# Power.net
KiCad netlist of a schematic drawn in Altium Designer
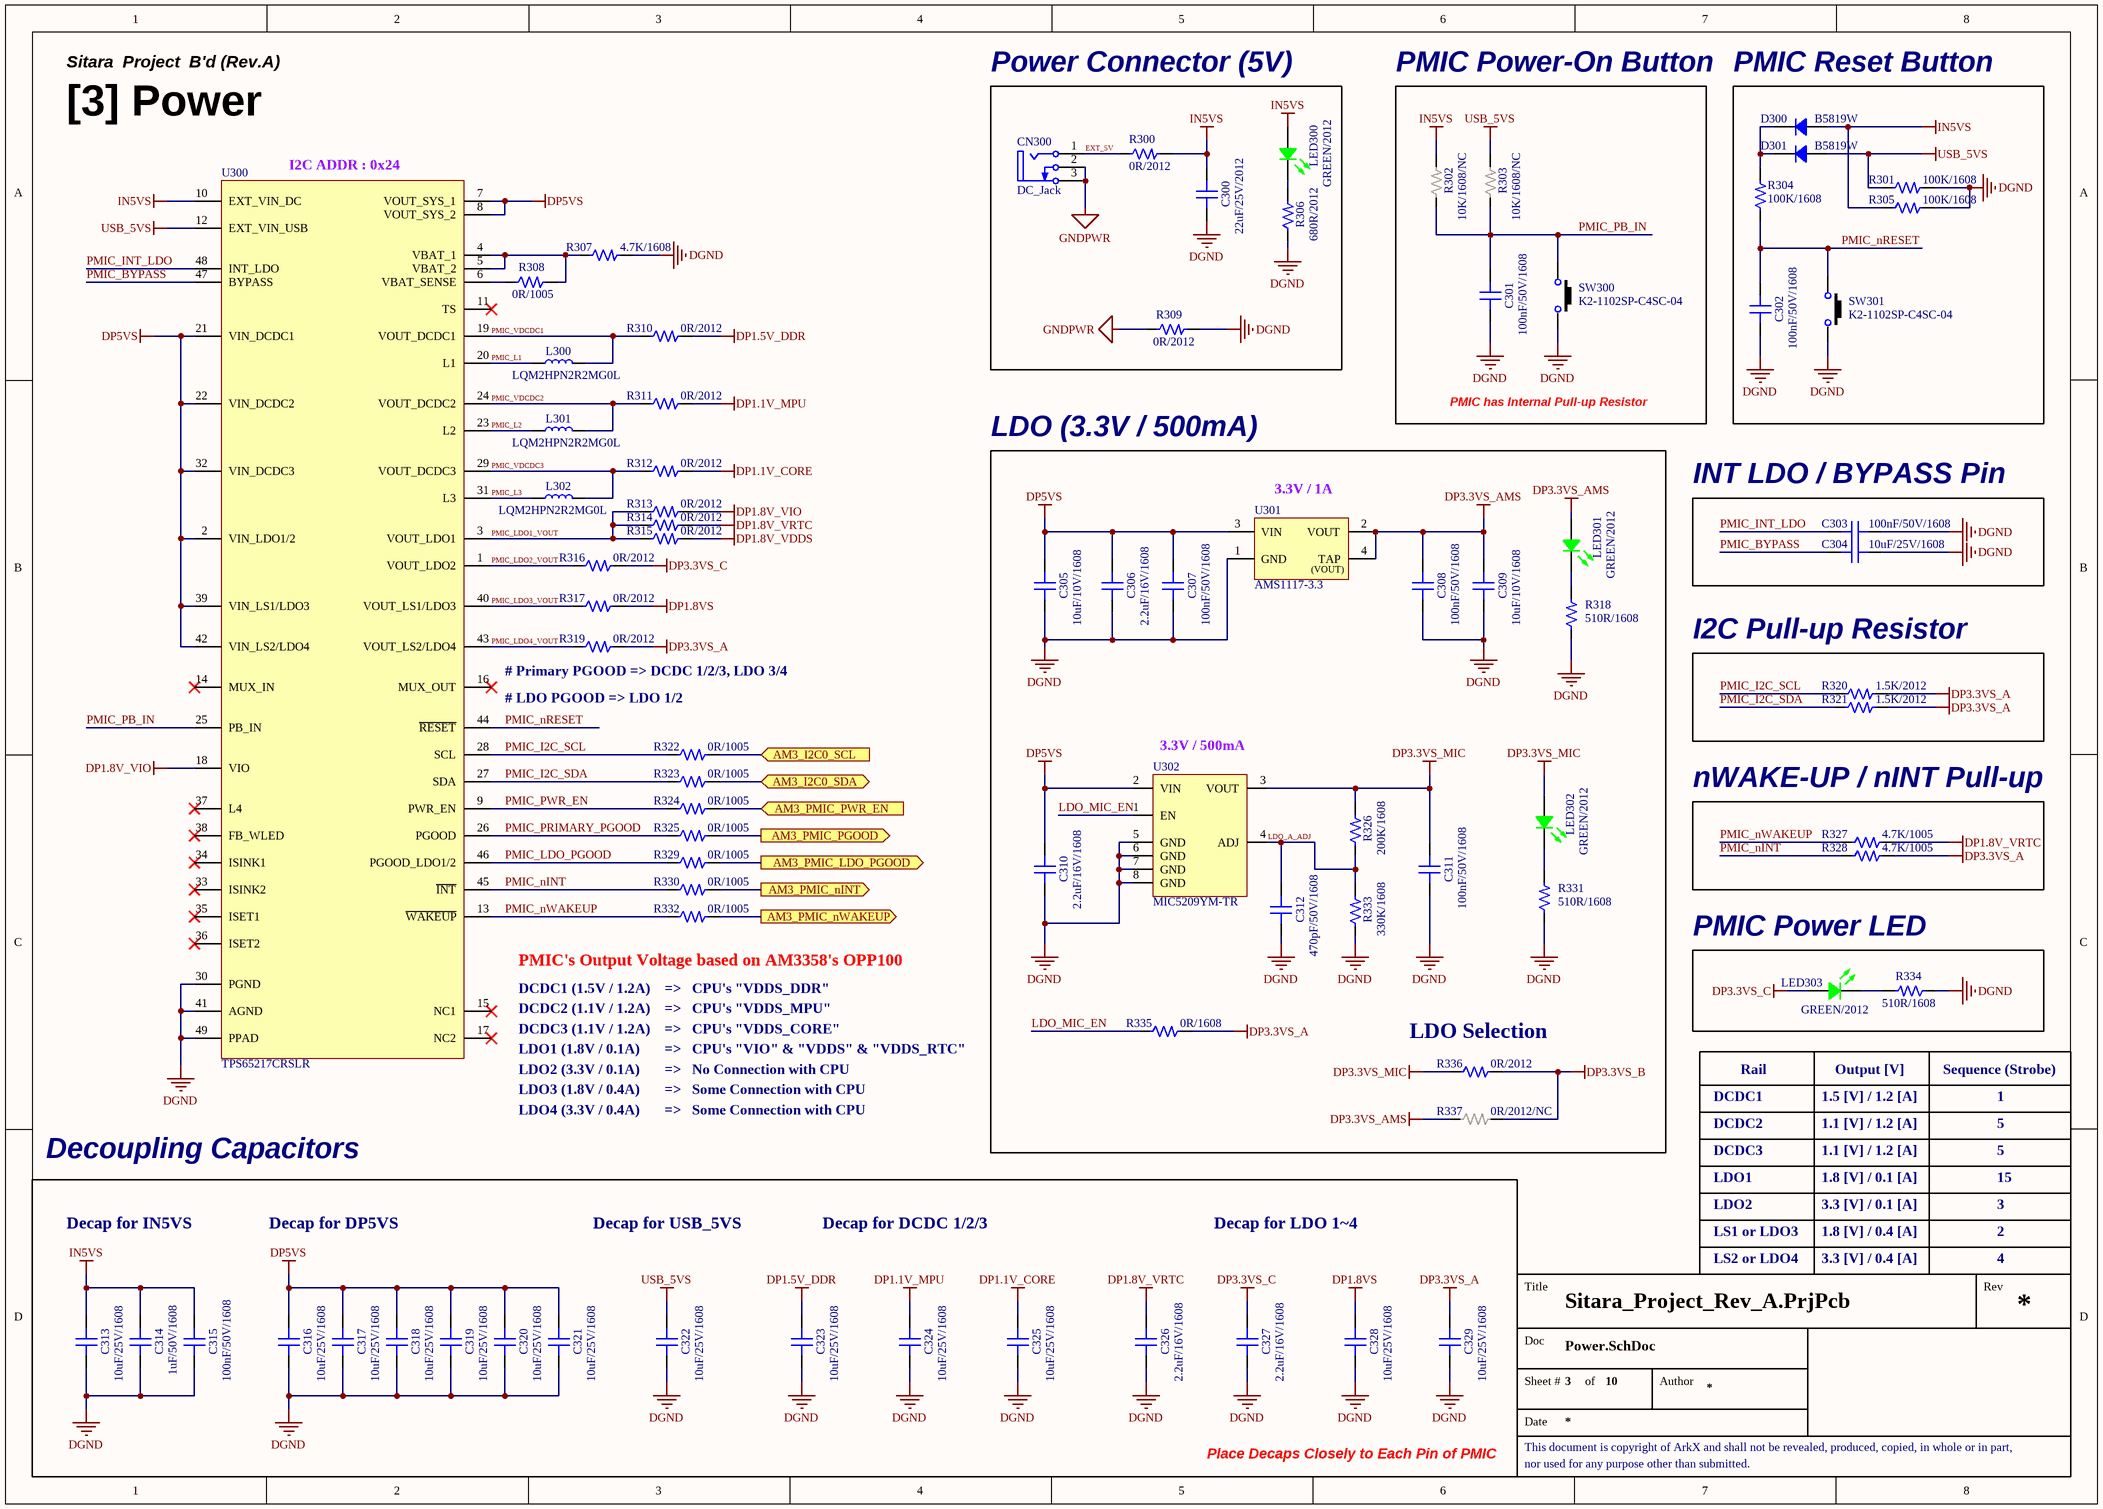
[diagram p0: Power.SchDoc]

(export (version "E")
  (design (tool "Eeschema 10.0.6"))
  (components
    (comp (ref "C300")
      (value "22uF/25V/2012")
      (footprint "CAP 2012 (0805_INCH)")
      (description "Ceramic CAP_22uF/25V/2012")
      (fields (field (name "LCSC PART #") "C45783"))
      (libsource (lib "Arkx") (part "CAP_22uF/25V/2012"))
    )
    (comp (ref "C301")
      (value "100nF/50V/1608")
      (footprint "CAP 1608 (0603_INCH)")
      (description "Ceramic CAP_100nF/50V/1608")
      (fields (field (name "LCSC PART #") "C14663"))
      (libsource (lib "Arkx") (part "CAP_100nF/50V/1608"))
    )
    (comp (ref "C302")
      (value "100nF/50V/1608")
      (footprint "CAP 1608 (0603_INCH)")
      (description "Ceramic CAP_100nF/50V/1608")
      (fields (field (name "LCSC PART #") "C14663"))
      (libsource (lib "Arkx") (part "CAP_100nF/50V/1608"))
    )
    (comp (ref "C303")
      (value "100nF/50V/1608")
      (footprint "CAP 1608 (0603_INCH)")
      (description "Ceramic CAP_100nF/50V/1608")
      (fields (field (name "LCSC PART #") "C14663"))
      (libsource (lib "Arkx") (part "CAP_100nF/50V/1608"))
    )
    (comp (ref "C304")
      (value "10uF/25V/1608")
      (footprint "CAP 1608 (0603_INCH)")
      (description "Ceramic CAP_10uF/25V/1608")
      (fields (field (name "LCSC PART #") "C96446"))
      (libsource (lib "Arkx") (part "CAP_10uF/25V/1608"))
    )
    (comp (ref "C305")
      (value "10uF/10V/1608")
      (footprint "CAP 1608 (0603_INCH)")
      (description "Ceramic CAP_10uF/10V/1608")
      (fields (field (name "LCSC PART #") "C19702"))
      (libsource (lib "Arkx") (part "CAP_10uF/10V/1608"))
    )
    (comp (ref "C306")
      (value "2.2uF/16V/1608")
      (footprint "CAP 1608 (0603_INCH)")
      (description "Ceramic CAP_2.2uF/16V/1608")
      (fields (field (name "LCSC PART #") "C23630"))
      (libsource (lib "Arkx") (part "CAP_2.2uF/16V/1608"))
    )
    (comp (ref "C307")
      (value "100nF/50V/1608")
      (footprint "CAP 1608 (0603_INCH)")
      (description "Ceramic CAP_100nF/50V/1608")
      (fields (field (name "LCSC PART #") "C14663"))
      (libsource (lib "Arkx") (part "CAP_100nF/50V/1608"))
    )
    (comp (ref "C308")
      (value "100nF/50V/1608")
      (footprint "CAP 1608 (0603_INCH)")
      (description "Ceramic CAP_100nF/50V/1608")
      (fields (field (name "LCSC PART #") "C14663"))
      (libsource (lib "Arkx") (part "CAP_100nF/50V/1608"))
    )
    (comp (ref "C309")
      (value "10uF/10V/1608")
      (footprint "CAP 1608 (0603_INCH)")
      (description "Ceramic CAP_10uF/10V/1608")
      (fields (field (name "LCSC PART #") "C19702"))
      (libsource (lib "Arkx") (part "CAP_10uF/10V/1608"))
    )
    (comp (ref "C310")
      (value "2.2uF/16V/1608")
      (footprint "CAP 1608 (0603_INCH)")
      (description "Ceramic CAP_2.2uF/16V/1608")
      (fields (field (name "LCSC PART #") "C23630"))
      (libsource (lib "Arkx") (part "CAP_2.2uF/16V/1608"))
    )
    (comp (ref "C311")
      (value "100nF/50V/1608")
      (footprint "CAP 1608 (0603_INCH)")
      (description "Ceramic CAP_100nF/50V/1608")
      (fields (field (name "LCSC PART #") "C14663"))
      (libsource (lib "Arkx") (part "CAP_100nF/50V/1608"))
    )
    (comp (ref "C312")
      (value "470pF/50V/1608")
      (footprint "CAP 1608 (0603_INCH)")
      (description "Ceramic CAP_470pF/50V/1608")
      (fields (field (name "LCSC PART #") "C1620"))
      (libsource (lib "Arkx") (part "CAP_470pF/50V/1608"))
    )
    (comp (ref "C313")
      (value "10uF/25V/1608")
      (footprint "CAP 1608 (0603_INCH)")
      (description "Ceramic CAP_10uF/25V/1608")
      (fields (field (name "LCSC PART #") "C96446"))
      (libsource (lib "Arkx") (part "CAP_10uF/25V/1608"))
    )
    (comp (ref "C314")
      (value "1uF/50V/1608")
      (footprint "CAP 1608 (0603_INCH)")
      (description "Ceramic CAP_1uF/50V/1608")
      (fields (field (name "LCSC PART #") "C15849"))
      (libsource (lib "Arkx") (part "CAP_1uF/50V/1608"))
    )
    (comp (ref "C315")
      (value "100nF/50V/1608")
      (footprint "CAP 1608 (0603_INCH)")
      (description "Ceramic CAP_100nF/50V/1608")
      (fields (field (name "LCSC PART #") "C14663"))
      (libsource (lib "Arkx") (part "CAP_100nF/50V/1608"))
    )
    (comp (ref "C316")
      (value "10uF/25V/1608")
      (footprint "CAP 1608 (0603_INCH)")
      (description "Ceramic CAP_10uF/25V/1608")
      (fields (field (name "LCSC PART #") "C96446"))
      (libsource (lib "Arkx") (part "CAP_10uF/25V/1608"))
    )
    (comp (ref "C317")
      (value "10uF/25V/1608")
      (footprint "CAP 1608 (0603_INCH)")
      (description "Ceramic CAP_10uF/25V/1608")
      (fields (field (name "LCSC PART #") "C96446"))
      (libsource (lib "Arkx") (part "CAP_10uF/25V/1608"))
    )
    (comp (ref "C318")
      (value "10uF/25V/1608")
      (footprint "CAP 1608 (0603_INCH)")
      (description "Ceramic CAP_10uF/25V/1608")
      (fields (field (name "LCSC PART #") "C96446"))
      (libsource (lib "Arkx") (part "CAP_10uF/25V/1608"))
    )
    (comp (ref "C319")
      (value "10uF/25V/1608")
      (footprint "CAP 1608 (0603_INCH)")
      (description "Ceramic CAP_10uF/25V/1608")
      (fields (field (name "LCSC PART #") "C96446"))
      (libsource (lib "Arkx") (part "CAP_10uF/25V/1608"))
    )
    (comp (ref "C320")
      (value "10uF/25V/1608")
      (footprint "CAP 1608 (0603_INCH)")
      (description "Ceramic CAP_10uF/25V/1608")
      (fields (field (name "LCSC PART #") "C96446"))
      (libsource (lib "Arkx") (part "CAP_10uF/25V/1608"))
    )
    (comp (ref "C321")
      (value "10uF/25V/1608")
      (footprint "CAP 1608 (0603_INCH)")
      (description "Ceramic CAP_10uF/25V/1608")
      (fields (field (name "LCSC PART #") "C96446"))
      (libsource (lib "Arkx") (part "CAP_10uF/25V/1608"))
    )
    (comp (ref "C322")
      (value "10uF/25V/1608")
      (footprint "CAP 1608 (0603_INCH)")
      (description "Ceramic CAP_10uF/25V/1608")
      (fields (field (name "LCSC PART #") "C96446"))
      (libsource (lib "Arkx") (part "CAP_10uF/25V/1608"))
    )
    (comp (ref "C323")
      (value "10uF/25V/1608")
      (footprint "CAP 1608 (0603_INCH)")
      (description "Ceramic CAP_10uF/25V/1608")
      (fields (field (name "LCSC PART #") "C96446"))
      (libsource (lib "Arkx") (part "CAP_10uF/25V/1608"))
    )
    (comp (ref "C324")
      (value "10uF/25V/1608")
      (footprint "CAP 1608 (0603_INCH)")
      (description "Ceramic CAP_10uF/25V/1608")
      (fields (field (name "LCSC PART #") "C96446"))
      (libsource (lib "Arkx") (part "CAP_10uF/25V/1608"))
    )
    (comp (ref "C325")
      (value "10uF/25V/1608")
      (footprint "CAP 1608 (0603_INCH)")
      (description "Ceramic CAP_10uF/25V/1608")
      (fields (field (name "LCSC PART #") "C96446"))
      (libsource (lib "Arkx") (part "CAP_10uF/25V/1608"))
    )
    (comp (ref "C326")
      (value "2.2uF/16V/1608")
      (footprint "CAP 1608 (0603_INCH)")
      (description "Ceramic CAP_2.2uF/16V/1608")
      (fields (field (name "LCSC PART #") "C23630"))
      (libsource (lib "Arkx") (part "CAP_2.2uF/16V/1608"))
    )
    (comp (ref "C327")
      (value "2.2uF/16V/1608")
      (footprint "CAP 1608 (0603_INCH)")
      (description "Ceramic CAP_2.2uF/16V/1608")
      (fields (field (name "LCSC PART #") "C23630"))
      (libsource (lib "Arkx") (part "CAP_2.2uF/16V/1608"))
    )
    (comp (ref "C328")
      (value "10uF/25V/1608")
      (footprint "CAP 1608 (0603_INCH)")
      (description "Ceramic CAP_10uF/25V/1608")
      (fields (field (name "LCSC PART #") "C96446"))
      (libsource (lib "Arkx") (part "CAP_10uF/25V/1608"))
    )
    (comp (ref "C329")
      (value "10uF/25V/1608")
      (footprint "CAP 1608 (0603_INCH)")
      (description "Ceramic CAP_10uF/25V/1608")
      (fields (field (name "LCSC PART #") "C96446"))
      (libsource (lib "Arkx") (part "CAP_10uF/25V/1608"))
    )
    (comp (ref "CN300")
      (value "DC_Jack")
      (footprint "CON_DC-JACK")
      (libsource (lib "Arkx") (part "CON_DC-Jack"))
    )
    (comp (ref "D300")
      (value "B5819W")
      (footprint "DIO_SOD-123")
      (description "40V 600mV@1A 1A SOD-123  Schottky Barrier Diodes (SBD) ROHS")
      (fields (field (name "LCSC PART #") "C8598"))
      (libsource (lib "Arkx") (part "DIO_B5819W"))
    )
    (comp (ref "D301")
      (value "B5819W")
      (footprint "DIO_SOD-123")
      (description "40V 600mV@1A 1A SOD-123  Schottky Barrier Diodes (SBD) ROHS")
      (fields (field (name "LCSC PART #") "C8598"))
      (libsource (lib "Arkx") (part "DIO_B5819W"))
    )
    (comp (ref "L300")
      (value "LQM2HPN2R2MG0L")
      (footprint "IND_LQM2HPN2R2MG0L")
      (description "2.2 µH Shielded Multilayer Inductor 1.3 A 100mOhm Max 1008 (2520 Metric)")
      (fields (field (name "LCSC PART #") "C86092"))
      (libsource (lib "Arkx") (part "IND_LQM2HPN2R2MG0L"))
    )
    (comp (ref "L301")
      (value "LQM2HPN2R2MG0L")
      (footprint "IND_LQM2HPN2R2MG0L")
      (description "2.2 µH Shielded Multilayer Inductor 1.3 A 100mOhm Max 1008 (2520 Metric)")
      (fields (field (name "LCSC PART #") "C86092"))
      (libsource (lib "Arkx") (part "IND_LQM2HPN2R2MG0L"))
    )
    (comp (ref "L302")
      (value "LQM2HPN2R2MG0L")
      (footprint "IND_LQM2HPN2R2MG0L")
      (description "2.2 µH Shielded Multilayer Inductor 1.3 A 100mOhm Max 1008 (2520 Metric)")
      (fields (field (name "LCSC PART #") "C86092"))
      (libsource (lib "Arkx") (part "IND_LQM2HPN2R2MG0L"))
    )
    (comp (ref "LED300")
      (value "GREEN/2012")
      (footprint "LED MHT170RGBCT (GREEN)")
      (fields (field (name "LCSC PART #") "C2962094"))
      (libsource (lib "Arkx") (part "LED_MHT170RGBCT(GREEN)"))
    )
    (comp (ref "LED301")
      (value "GREEN/2012")
      (footprint "LED MHT170RGBCT (GREEN)")
      (fields (field (name "LCSC PART #") "C2962094"))
      (libsource (lib "Arkx") (part "LED_MHT170RGBCT(GREEN)"))
    )
    (comp (ref "LED302")
      (value "GREEN/2012")
      (footprint "LED MHT170RGBCT (GREEN)")
      (fields (field (name "LCSC PART #") "C2962094"))
      (libsource (lib "Arkx") (part "LED_MHT170RGBCT(GREEN)"))
    )
    (comp (ref "LED303")
      (value "GREEN/2012")
      (footprint "LED MHT170RGBCT (GREEN)")
      (fields (field (name "LCSC PART #") "C2962094"))
      (libsource (lib "Arkx") (part "LED_MHT170RGBCT(GREEN)"))
    )
    (comp (ref "R300")
      (value "0R/2012")
      (footprint "RES 2012 (0805_inch)")
      (description "RES_0R/2012/0.125W")
      (fields (field (name "LCSC PART #") "C17477"))
      (libsource (lib "Arkx") (part "RES_0R/2012/0.125W"))
    )
    (comp (ref "R301")
      (value "100K/1608")
      (footprint "RES 1608 (0603_inch)")
      (description "RES_100K/1608/0.1W")
      (fields (field (name "LCSC PART #") "C25803"))
      (libsource (lib "Arkx") (part "RES_100K/1608/0.1W"))
    )
    (comp (ref "R302")
      (value "10K/1608/NC")
      (footprint "RES 1608 (0603_inch)/NC")
      (description "RES_10K/1608/0.1W")
      (libsource (lib "Arkx") (part "RES_NC_10K/1608/0.1W"))
    )
    (comp (ref "R303")
      (value "10K/1608/NC")
      (footprint "RES 1608 (0603_inch)/NC")
      (description "RES_10K/1608/0.1W")
      (libsource (lib "Arkx") (part "RES_NC_10K/1608/0.1W"))
    )
    (comp (ref "R304")
      (value "100K/1608")
      (footprint "RES 1608 (0603_inch)")
      (description "RES_100K/1608/0.1W")
      (fields (field (name "LCSC PART #") "C25803"))
      (libsource (lib "Arkx") (part "RES_100K/1608/0.1W"))
    )
    (comp (ref "R305")
      (value "100K/1608")
      (footprint "RES 1608 (0603_inch)")
      (description "RES_100K/1608/0.1W")
      (fields (field (name "LCSC PART #") "C25803"))
      (libsource (lib "Arkx") (part "RES_100K/1608/0.1W"))
    )
    (comp (ref "R306")
      (value "680R/2012")
      (footprint "RES 2012 (0805_inch)")
      (description "RES_680R/2012/0.125W")
      (fields (field (name "LCSC PART #") "C17798"))
      (libsource (lib "Arkx") (part "RES_680R/2012/0.125W"))
    )
    (comp (ref "R307")
      (value "4.7K/1608")
      (footprint "RES 1608 (0603_inch)")
      (description "RES_4.7K/1608/0.1W")
      (fields (field (name "LCSC PART #") "C23162"))
      (libsource (lib "Arkx") (part "RES_4.7K/1608/0.1W"))
    )
    (comp (ref "R308")
      (value "0R/1005")
      (footprint "RES 1005 (0402_inch)")
      (description "RES_0R/1005/62.5mW")
      (fields (field (name "LCSC PART #") "C17168"))
      (libsource (lib "Arkx") (part "RES_0R/1005/62.5mW"))
    )
    (comp (ref "R309")
      (value "0R/2012")
      (footprint "RES 2012 (0805_inch)")
      (description "RES_0R/2012/0.125W")
      (fields (field (name "LCSC PART #") "C17477"))
      (libsource (lib "Arkx") (part "RES_0R/2012/0.125W"))
    )
    (comp (ref "R310")
      (value "0R/2012")
      (footprint "RES 2012 (0805_inch)")
      (description "RES_0R/2012/0.125W")
      (fields (field (name "LCSC PART #") "C17477"))
      (libsource (lib "Arkx") (part "RES_0R/2012/0.125W"))
    )
    (comp (ref "R311")
      (value "0R/2012")
      (footprint "RES 2012 (0805_inch)")
      (description "RES_0R/2012/0.125W")
      (fields (field (name "LCSC PART #") "C17477"))
      (libsource (lib "Arkx") (part "RES_0R/2012/0.125W"))
    )
    (comp (ref "R312")
      (value "0R/2012")
      (footprint "RES 2012 (0805_inch)")
      (description "RES_0R/2012/0.125W")
      (fields (field (name "LCSC PART #") "C17477"))
      (libsource (lib "Arkx") (part "RES_0R/2012/0.125W"))
    )
    (comp (ref "R313")
      (value "0R/2012")
      (footprint "RES 2012 (0805_inch)")
      (description "RES_0R/2012/0.125W")
      (fields (field (name "LCSC PART #") "C17477"))
      (libsource (lib "Arkx") (part "RES_0R/2012/0.125W"))
    )
    (comp (ref "R314")
      (value "0R/2012")
      (footprint "RES 2012 (0805_inch)")
      (description "RES_0R/2012/0.125W")
      (fields (field (name "LCSC PART #") "C17477"))
      (libsource (lib "Arkx") (part "RES_0R/2012/0.125W"))
    )
    (comp (ref "R315")
      (value "0R/2012")
      (footprint "RES 2012 (0805_inch)")
      (description "RES_0R/2012/0.125W")
      (fields (field (name "LCSC PART #") "C17477"))
      (libsource (lib "Arkx") (part "RES_0R/2012/0.125W"))
    )
    (comp (ref "R316")
      (value "0R/2012")
      (footprint "RES 2012 (0805_inch)")
      (description "RES_0R/2012/0.125W")
      (fields (field (name "LCSC PART #") "C17477"))
      (libsource (lib "Arkx") (part "RES_0R/2012/0.125W"))
    )
    (comp (ref "R317")
      (value "0R/2012")
      (footprint "RES 2012 (0805_inch)")
      (description "RES_0R/2012/0.125W")
      (fields (field (name "LCSC PART #") "C17477"))
      (libsource (lib "Arkx") (part "RES_0R/2012/0.125W"))
    )
    (comp (ref "R318")
      (value "510R/1608")
      (footprint "RES 1608 (0603_inch)")
      (description "RES_510R/1608/0.1W")
      (fields (field (name "LCSC PART #") "C23193"))
      (libsource (lib "Arkx") (part "RES_510R/1608/0.1W"))
    )
    (comp (ref "R319")
      (value "0R/2012")
      (footprint "RES 2012 (0805_inch)")
      (description "RES_0R/2012/0.125W")
      (fields (field (name "LCSC PART #") "C17477"))
      (libsource (lib "Arkx") (part "RES_0R/2012/0.125W"))
    )
    (comp (ref "R320")
      (value "1.5K/2012")
      (footprint "RES 2012 (0805_inch)")
      (description "RES_1.5K/2012/0.125W")
      (fields (field (name "LCSC PART #") "C4310"))
      (libsource (lib "Arkx") (part "RES_1.5K/2012/0.125W"))
    )
    (comp (ref "R321")
      (value "1.5K/2012")
      (footprint "RES 2012 (0805_inch)")
      (description "RES_1.5K/2012/0.125W")
      (fields (field (name "LCSC PART #") "C4310"))
      (libsource (lib "Arkx") (part "RES_1.5K/2012/0.125W"))
    )
    (comp (ref "R322")
      (value "0R/1005")
      (footprint "RES 1005 (0402_inch)")
      (description "RES_0R/1005/62.5mW")
      (fields (field (name "LCSC PART #") "C17168"))
      (libsource (lib "Arkx") (part "RES_0R/1005/62.5mW"))
    )
    (comp (ref "R323")
      (value "0R/1005")
      (footprint "RES 1005 (0402_inch)")
      (description "RES_0R/1005/62.5mW")
      (fields (field (name "LCSC PART #") "C17168"))
      (libsource (lib "Arkx") (part "RES_0R/1005/62.5mW"))
    )
    (comp (ref "R324")
      (value "0R/1005")
      (footprint "RES 1005 (0402_inch)")
      (description "RES_0R/1005/62.5mW")
      (fields (field (name "LCSC PART #") "C17168"))
      (libsource (lib "Arkx") (part "RES_0R/1005/62.5mW"))
    )
    (comp (ref "R325")
      (value "0R/1005")
      (footprint "RES 1005 (0402_inch)")
      (description "RES_0R/1005/62.5mW")
      (fields (field (name "LCSC PART #") "C17168"))
      (libsource (lib "Arkx") (part "RES_0R/1005/62.5mW"))
    )
    (comp (ref "R326")
      (value "200K/1608")
      (footprint "RES 1608 (0603_inch)")
      (description "RES_200K/1608/0.1W")
      (fields (field (name "LCSC PART #") "C25811"))
      (libsource (lib "Arkx") (part "RES_200K/1608/0.1W"))
    )
    (comp (ref "R327")
      (value "4.7K/1005")
      (footprint "RES 1005 (0402_inch)")
      (description "RES_4.7K/1005/62.5mW")
      (fields (field (name "LCSC PART #") "C25900"))
      (libsource (lib "Arkx") (part "RES_4.7K/1005/62.5mW"))
    )
    (comp (ref "R328")
      (value "4.7K/1005")
      (footprint "RES 1005 (0402_inch)")
      (description "RES_4.7K/1005/62.5mW")
      (fields (field (name "LCSC PART #") "C25900"))
      (libsource (lib "Arkx") (part "RES_4.7K/1005/62.5mW"))
    )
    (comp (ref "R329")
      (value "0R/1005")
      (footprint "RES 1005 (0402_inch)")
      (description "RES_0R/1005/62.5mW")
      (fields (field (name "LCSC PART #") "C17168"))
      (libsource (lib "Arkx") (part "RES_0R/1005/62.5mW"))
    )
    (comp (ref "R330")
      (value "0R/1005")
      (footprint "RES 1005 (0402_inch)")
      (description "RES_0R/1005/62.5mW")
      (fields (field (name "LCSC PART #") "C17168"))
      (libsource (lib "Arkx") (part "RES_0R/1005/62.5mW"))
    )
    (comp (ref "R331")
      (value "510R/1608")
      (footprint "RES 1608 (0603_inch)")
      (description "RES_510R/1608/0.1W")
      (fields (field (name "LCSC PART #") "C23193"))
      (libsource (lib "Arkx") (part "RES_510R/1608/0.1W"))
    )
    (comp (ref "R332")
      (value "0R/1005")
      (footprint "RES 1005 (0402_inch)")
      (description "RES_0R/1005/62.5mW")
      (fields (field (name "LCSC PART #") "C17168"))
      (libsource (lib "Arkx") (part "RES_0R/1005/62.5mW"))
    )
    (comp (ref "R333")
      (value "330K/1608")
      (footprint "RES 1608 (0603_inch)")
      (description "RES_330K/1608/0.1W")
      (fields (field (name "LCSC PART #") "C23137"))
      (libsource (lib "Arkx") (part "RES_330K/1608/0.1W"))
    )
    (comp (ref "R334")
      (value "510R/1608")
      (footprint "RES 1608 (0603_inch)")
      (description "RES_510R/1608/0.1W")
      (fields (field (name "LCSC PART #") "C23193"))
      (libsource (lib "Arkx") (part "RES_510R/1608/0.1W"))
    )
    (comp (ref "R335")
      (value "0R/1608")
      (footprint "RES 1608 (0603_inch)")
      (description "RES_0R/1608/0.1W")
      (fields (field (name "LCSC PART #") "C21189"))
      (libsource (lib "Arkx") (part "RES_0R/1608/0.1W"))
    )
    (comp (ref "R336")
      (value "0R/2012")
      (footprint "RES 2012 (0805_inch)")
      (description "RES_0R/2012/0.125W")
      (fields (field (name "LCSC PART #") "C17477"))
      (libsource (lib "Arkx") (part "RES_0R/2012/0.125W"))
    )
    (comp (ref "R337")
      (value "0R/2012/NC")
      (footprint "RES 2012 (0805_INCH)/NC")
      (description "0R/2012/0.125W/NC")
      (libsource (lib "Arkx") (part "RES_NC_0R/2012/0.125W"))
    )
    (comp (ref "SW300")
      (value "K2-1102SP-C4SC-04")
      (footprint "SW K2-1102SP-C4SC-04")
      (fields (field (name "LCSC PART #") "C127509"))
      (libsource (lib "Arkx") (part "SW_K2-1102SP-C4SC-04(2P)"))
    )
    (comp (ref "SW301")
      (value "K2-1102SP-C4SC-04")
      (footprint "SW K2-1102SP-C4SC-04")
      (fields (field (name "LCSC PART #") "C127509"))
      (libsource (lib "Arkx") (part "SW_K2-1102SP-C4SC-04(2P)"))
    )
    (comp (ref "U300")
      (value "TPS65217CRSLR")
      (footprint "IC_VQFN-48(6x6)")
      (fields (field (name "LCSC PART #") "C116081"))
      (libsource (lib "Arkx") (part "IC_PMIC_TPS65217CRSLR"))
    )
    (comp (ref "U301")
      (value "AMS1117-3.3")
      (footprint "SOT 223-3 (DIODES INCORPORATED)")
      (fields (field (name "LCSC PART #") "C6186"))
      (libsource (lib "Arkx") (part "IC_REG_AMS1117-3.3"))
    )
    (comp (ref "U302")
      (value "MIC5209YM-TR")
      (footprint "IC_SOIC-8 (4.90x3.90mm)")
      (description "Linear Voltage Regulator IC Positive Adjustable 1 Output 500mA 8-SOIC")
      (fields (field (name "LCSC PART #") "C461593"))
      (libsource (lib "Arkx") (part "IC_REG_MIC5209YM-TR"))
    )
  )
  (nets
    (net (code "1") (name "/AM3_I2C0_SCL") (class "Default")
      (node (ref "R322") (pin "2") (pinfunction "2_2") (pintype "passive"))
    )
    (net (code "2") (name "/AM3_I2C0_SDA") (class "Default")
      (node (ref "R323") (pin "2") (pinfunction "2_2") (pintype "passive"))
    )
    (net (code "3") (name "/AM3_PMIC_LDO_PGOOD") (class "Default")
      (node (ref "R329") (pin "2") (pinfunction "2_2") (pintype "passive"))
    )
    (net (code "4") (name "/AM3_PMIC_PGOOD") (class "Default")
      (node (ref "R325") (pin "2") (pinfunction "2_2") (pintype "passive"))
    )
    (net (code "5") (name "/AM3_PMIC_PWR_EN") (class "Default")
      (node (ref "R324") (pin "2") (pinfunction "2_2") (pintype "passive"))
    )
    (net (code "6") (name "/AM3_PMIC_nINT") (class "Default")
      (node (ref "R330") (pin "2") (pinfunction "2_2") (pintype "passive"))
    )
    (net (code "7") (name "/AM3_PMIC_nWAKEUP") (class "Default")
      (node (ref "R332") (pin "2") (pinfunction "2_2") (pintype "passive"))
    )
    (net (code "8") (name "/EXT_5V") (class "Default")
      (node (ref "CN300") (pin "1") (pinfunction "VCC_1") (pintype "power_in"))
      (node (ref "R300") (pin "1") (pinfunction "1_1") (pintype "passive"))
    )
    (net (code "9") (name "/LDO_A_ADJ") (class "Default")
      (node (ref "C312") (pin "2") (pinfunction "2_2") (pintype "passive"))
      (node (ref "R326") (pin "1") (pinfunction "1_1") (pintype "passive"))
      (node (ref "R333") (pin "2") (pinfunction "2_2") (pintype "passive"))
      (node (ref "U302") (pin "4") (pinfunction "ADJ_4") (pintype "passive"))
    )
    (net (code "10") (name "/LDO_MIC_EN") (class "Default")
      (node (ref "R335") (pin "1") (pinfunction "1_1") (pintype "passive"))
      (node (ref "U302") (pin "1") (pinfunction "EN_1") (pintype "passive"))
    )
    (net (code "11") (name "/PMIC_BYPASS") (class "Default")
      (node (ref "C304") (pin "1") (pinfunction "1_1") (pintype "passive"))
      (node (ref "U300") (pin "47") (pinfunction "BYPASS_47") (pintype "passive"))
    )
    (net (code "12") (name "/PMIC_I2C_SCL") (class "Default")
      (node (ref "R320") (pin "1") (pinfunction "1_1") (pintype "passive"))
      (node (ref "R322") (pin "1") (pinfunction "1_1") (pintype "passive"))
      (node (ref "U300") (pin "28") (pinfunction "SCL_28") (pintype "passive"))
    )
    (net (code "13") (name "/PMIC_I2C_SDA") (class "Default")
      (node (ref "R321") (pin "1") (pinfunction "1_1") (pintype "passive"))
      (node (ref "R323") (pin "1") (pinfunction "1_1") (pintype "passive"))
      (node (ref "U300") (pin "27") (pinfunction "SDA_27") (pintype "passive"))
    )
    (net (code "14") (name "/PMIC_INT_LDO") (class "Default")
      (node (ref "C303") (pin "2") (pinfunction "2_2") (pintype "passive"))
      (node (ref "U300") (pin "48") (pinfunction "INT_LDO_48") (pintype "passive"))
    )
    (net (code "15") (name "/PMIC_L1") (class "Default")
      (node (ref "L300") (pin "1") (pinfunction "1_1") (pintype "passive"))
      (node (ref "U300") (pin "20") (pinfunction "L1_20") (pintype "passive"))
    )
    (net (code "16") (name "/PMIC_L2") (class "Default")
      (node (ref "L301") (pin "1") (pinfunction "1_1") (pintype "passive"))
      (node (ref "U300") (pin "23") (pinfunction "L2_23") (pintype "passive"))
    )
    (net (code "17") (name "/PMIC_L3") (class "Default")
      (node (ref "L302") (pin "1") (pinfunction "1_1") (pintype "passive"))
      (node (ref "U300") (pin "31") (pinfunction "L3_31") (pintype "passive"))
    )
    (net (code "18") (name "/PMIC_LDO1_VOUT") (class "Default")
      (node (ref "R313") (pin "1") (pinfunction "1_1") (pintype "passive"))
      (node (ref "R314") (pin "1") (pinfunction "1_1") (pintype "passive"))
      (node (ref "R315") (pin "1") (pinfunction "1_1") (pintype "passive"))
      (node (ref "U300") (pin "3") (pinfunction "VOUT_LDO1_3") (pintype "passive"))
    )
    (net (code "19") (name "/PMIC_LDO2_VOUT") (class "Default")
      (node (ref "R316") (pin "1") (pinfunction "1_1") (pintype "passive"))
      (node (ref "U300") (pin "1") (pinfunction "VOUT_LDO2_1") (pintype "passive"))
    )
    (net (code "20") (name "/PMIC_LDO3_VOUT") (class "Default")
      (node (ref "R317") (pin "1") (pinfunction "1_1") (pintype "passive"))
      (node (ref "U300") (pin "40") (pinfunction "VOUT_LS1/LDO3_40") (pintype "passive"))
    )
    (net (code "21") (name "/PMIC_LDO4_VOUT") (class "Default")
      (node (ref "R319") (pin "1") (pinfunction "1_1") (pintype "passive"))
      (node (ref "U300") (pin "43") (pinfunction "VOUT_LS2/LDO4_43") (pintype "passive"))
    )
    (net (code "22") (name "/PMIC_LDO_PGOOD") (class "Default")
      (node (ref "R329") (pin "1") (pinfunction "1_1") (pintype "passive"))
      (node (ref "U300") (pin "46") (pinfunction "PGOOD_LDO1/2_46") (pintype "passive"))
    )
    (net (code "23") (name "/PMIC_PB_IN") (class "Default")
      (node (ref "C301") (pin "2") (pinfunction "2_2") (pintype "passive"))
      (node (ref "R302") (pin "1") (pinfunction "1_1") (pintype "passive"))
      (node (ref "R303") (pin "1") (pinfunction "1_1") (pintype "passive"))
      (node (ref "SW300") (pin "1") (pinfunction "1_1") (pintype "passive"))
      (node (ref "U300") (pin "25") (pinfunction "PB_IN_25") (pintype "passive"))
    )
    (net (code "24") (name "/PMIC_PRIMARY_PGOOD") (class "Default")
      (node (ref "R325") (pin "1") (pinfunction "1_1") (pintype "passive"))
      (node (ref "U300") (pin "26") (pinfunction "PGOOD_26") (pintype "passive"))
    )
    (net (code "25") (name "/PMIC_PWR_EN") (class "Default")
      (node (ref "R324") (pin "1") (pinfunction "1_1") (pintype "passive"))
      (node (ref "U300") (pin "9") (pinfunction "PWR_EN_9") (pintype "passive"))
    )
    (net (code "26") (name "/PMIC_VDCDC1") (class "Default")
      (node (ref "L300") (pin "2") (pinfunction "2_2") (pintype "passive"))
      (node (ref "R310") (pin "1") (pinfunction "1_1") (pintype "passive"))
      (node (ref "U300") (pin "19") (pinfunction "VOUT_DCDC1_19") (pintype "passive"))
    )
    (net (code "27") (name "/PMIC_VDCDC2") (class "Default")
      (node (ref "L301") (pin "2") (pinfunction "2_2") (pintype "passive"))
      (node (ref "R311") (pin "1") (pinfunction "1_1") (pintype "passive"))
      (node (ref "U300") (pin "24") (pinfunction "VOUT_DCDC2_24") (pintype "passive"))
    )
    (net (code "28") (name "/PMIC_VDCDC3") (class "Default")
      (node (ref "L302") (pin "2") (pinfunction "2_2") (pintype "passive"))
      (node (ref "R312") (pin "1") (pinfunction "1_1") (pintype "passive"))
      (node (ref "U300") (pin "29") (pinfunction "VOUT_DCDC3_29") (pintype "passive"))
    )
    (net (code "29") (name "/PMIC_nINT") (class "Default")
      (node (ref "R328") (pin "1") (pinfunction "1_1") (pintype "passive"))
      (node (ref "R330") (pin "1") (pinfunction "1_1") (pintype "passive"))
      (node (ref "U300") (pin "45") (pinfunction "~{INT}_45") (pintype "passive"))
    )
    (net (code "30") (name "/PMIC_nRESET") (class "Default")
      (node (ref "C302") (pin "2") (pinfunction "2_2") (pintype "passive"))
      (node (ref "R304") (pin "1") (pinfunction "1_1") (pintype "passive"))
      (node (ref "SW301") (pin "1") (pinfunction "1_1") (pintype "passive"))
      (node (ref "U300") (pin "44") (pinfunction "~{RESET}_44") (pintype "passive"))
    )
    (net (code "31") (name "/PMIC_nWAKEUP") (class "Default")
      (node (ref "R327") (pin "1") (pinfunction "1_1") (pintype "passive"))
      (node (ref "R332") (pin "1") (pinfunction "1_1") (pintype "passive"))
      (node (ref "U300") (pin "13") (pinfunction "~{WAKEUP}_13") (pintype "passive"))
    )
    (net (code "32") (name "DGND") (class "Default")
      (node (ref "C300") (pin "1") (pinfunction "1_1") (pintype "passive"))
      (node (ref "C301") (pin "1") (pinfunction "1_1") (pintype "passive"))
      (node (ref "C302") (pin "1") (pinfunction "1_1") (pintype "passive"))
      (node (ref "C303") (pin "1") (pinfunction "1_1") (pintype "passive"))
      (node (ref "C304") (pin "2") (pinfunction "2_2") (pintype "passive"))
      (node (ref "C305") (pin "1") (pinfunction "1_1") (pintype "passive"))
      (node (ref "C306") (pin "1") (pinfunction "1_1") (pintype "passive"))
      (node (ref "C307") (pin "1") (pinfunction "1_1") (pintype "passive"))
      (node (ref "C308") (pin "1") (pinfunction "1_1") (pintype "passive"))
      (node (ref "C309") (pin "1") (pinfunction "1_1") (pintype "passive"))
      (node (ref "C310") (pin "1") (pinfunction "1_1") (pintype "passive"))
      (node (ref "C311") (pin "1") (pinfunction "1_1") (pintype "passive"))
      (node (ref "C312") (pin "1") (pinfunction "1_1") (pintype "passive"))
      (node (ref "C313") (pin "1") (pinfunction "1_1") (pintype "passive"))
      (node (ref "C314") (pin "1") (pinfunction "1_1") (pintype "passive"))
      (node (ref "C315") (pin "1") (pinfunction "1_1") (pintype "passive"))
      (node (ref "C316") (pin "1") (pinfunction "1_1") (pintype "passive"))
      (node (ref "C317") (pin "1") (pinfunction "1_1") (pintype "passive"))
      (node (ref "C318") (pin "1") (pinfunction "1_1") (pintype "passive"))
      (node (ref "C319") (pin "1") (pinfunction "1_1") (pintype "passive"))
      (node (ref "C320") (pin "1") (pinfunction "1_1") (pintype "passive"))
      (node (ref "C321") (pin "1") (pinfunction "1_1") (pintype "passive"))
      (node (ref "C322") (pin "1") (pinfunction "1_1") (pintype "passive"))
      (node (ref "C323") (pin "1") (pinfunction "1_1") (pintype "passive"))
      (node (ref "C324") (pin "1") (pinfunction "1_1") (pintype "passive"))
      (node (ref "C325") (pin "1") (pinfunction "1_1") (pintype "passive"))
      (node (ref "C326") (pin "1") (pinfunction "1_1") (pintype "passive"))
      (node (ref "C327") (pin "1") (pinfunction "1_1") (pintype "passive"))
      (node (ref "C328") (pin "1") (pinfunction "1_1") (pintype "passive"))
      (node (ref "C329") (pin "1") (pinfunction "1_1") (pintype "passive"))
      (node (ref "R301") (pin "2") (pinfunction "2_2") (pintype "passive"))
      (node (ref "R305") (pin "2") (pinfunction "2_2") (pintype "passive"))
      (node (ref "R306") (pin "1") (pinfunction "1_1") (pintype "passive"))
      (node (ref "R307") (pin "2") (pinfunction "2_2") (pintype "passive"))
      (node (ref "R309") (pin "2") (pinfunction "2_2") (pintype "passive"))
      (node (ref "R318") (pin "1") (pinfunction "1_1") (pintype "passive"))
      (node (ref "R331") (pin "1") (pinfunction "1_1") (pintype "passive"))
      (node (ref "R333") (pin "1") (pinfunction "1_1") (pintype "passive"))
      (node (ref "R334") (pin "1") (pinfunction "1_1") (pintype "passive"))
      (node (ref "SW300") (pin "3") (pinfunction "3_3") (pintype "passive"))
      (node (ref "SW301") (pin "3") (pinfunction "3_3") (pintype "passive"))
      (node (ref "U300") (pin "30") (pinfunction "PGND_30") (pintype "passive"))
      (node (ref "U300") (pin "41") (pinfunction "AGND_41") (pintype "passive"))
      (node (ref "U300") (pin "49") (pinfunction "PPAD_49") (pintype "passive"))
      (node (ref "U301") (pin "1") (pinfunction "GND_1") (pintype "passive"))
      (node (ref "U302") (pin "5") (pinfunction "GND_5") (pintype "power_in"))
      (node (ref "U302") (pin "6") (pinfunction "GND_6") (pintype "power_in"))
      (node (ref "U302") (pin "7") (pinfunction "GND_7") (pintype "power_in"))
      (node (ref "U302") (pin "8") (pinfunction "GND_8") (pintype "power_in"))
    )
    (net (code "33") (name "DP1.1V_CORE") (class "Default")
      (node (ref "C325") (pin "2") (pinfunction "2_2") (pintype "passive"))
      (node (ref "R312") (pin "2") (pinfunction "2_2") (pintype "passive"))
    )
    (net (code "34") (name "DP1.1V_MPU") (class "Default")
      (node (ref "C324") (pin "2") (pinfunction "2_2") (pintype "passive"))
      (node (ref "R311") (pin "2") (pinfunction "2_2") (pintype "passive"))
    )
    (net (code "35") (name "DP1.5V_DDR") (class "Default")
      (node (ref "C323") (pin "2") (pinfunction "2_2") (pintype "passive"))
      (node (ref "R310") (pin "2") (pinfunction "2_2") (pintype "passive"))
    )
    (net (code "36") (name "DP1.8VS") (class "Default")
      (node (ref "C328") (pin "2") (pinfunction "2_2") (pintype "passive"))
      (node (ref "R317") (pin "2") (pinfunction "2_2") (pintype "passive"))
    )
    (net (code "37") (name "DP1.8V_VDDS") (class "Default")
      (node (ref "R315") (pin "2") (pinfunction "2_2") (pintype "passive"))
    )
    (net (code "38") (name "DP1.8V_VIO") (class "Default")
      (node (ref "R313") (pin "2") (pinfunction "2_2") (pintype "passive"))
      (node (ref "U300") (pin "18") (pinfunction "VIO_18") (pintype "passive"))
    )
    (net (code "39") (name "DP1.8V_VRTC") (class "Default")
      (node (ref "C326") (pin "2") (pinfunction "2_2") (pintype "passive"))
      (node (ref "R314") (pin "2") (pinfunction "2_2") (pintype "passive"))
      (node (ref "R327") (pin "2") (pinfunction "2_2") (pintype "passive"))
    )
    (net (code "40") (name "DP3.3VS_A") (class "Default")
      (node (ref "C329") (pin "2") (pinfunction "2_2") (pintype "passive"))
      (node (ref "R319") (pin "2") (pinfunction "2_2") (pintype "passive"))
      (node (ref "R320") (pin "2") (pinfunction "2_2") (pintype "passive"))
      (node (ref "R321") (pin "2") (pinfunction "2_2") (pintype "passive"))
      (node (ref "R328") (pin "2") (pinfunction "2_2") (pintype "passive"))
      (node (ref "R335") (pin "2") (pinfunction "2_2") (pintype "passive"))
    )
    (net (code "41") (name "DP3.3VS_AMS") (class "Default")
      (node (ref "C308") (pin "2") (pinfunction "2_2") (pintype "passive"))
      (node (ref "C309") (pin "2") (pinfunction "2_2") (pintype "passive"))
      (node (ref "LED301") (pin "4") (pinfunction "Common_Anode_4") (pintype "passive"))
      (node (ref "R337") (pin "1") (pinfunction "1_1") (pintype "passive"))
      (node (ref "U301") (pin "2") (pinfunction "VOUT_2") (pintype "passive"))
      (node (ref "U301") (pin "4") (pinfunction "TAP_4") (pintype "passive"))
    )
    (net (code "42") (name "DP3.3VS_B") (class "Default")
      (node (ref "R336") (pin "2") (pinfunction "2_2") (pintype "passive"))
      (node (ref "R337") (pin "2") (pinfunction "2_2") (pintype "passive"))
    )
    (net (code "43") (name "DP3.3VS_C") (class "Default")
      (node (ref "C327") (pin "2") (pinfunction "2_2") (pintype "passive"))
      (node (ref "LED303") (pin "4") (pinfunction "Common_Anode_4") (pintype "passive"))
      (node (ref "R316") (pin "2") (pinfunction "2_2") (pintype "passive"))
    )
    (net (code "44") (name "DP3.3VS_MIC") (class "Default")
      (node (ref "C311") (pin "2") (pinfunction "2_2") (pintype "passive"))
      (node (ref "LED302") (pin "4") (pinfunction "Common_Anode_4") (pintype "passive"))
      (node (ref "R326") (pin "2") (pinfunction "2_2") (pintype "passive"))
      (node (ref "R336") (pin "1") (pinfunction "1_1") (pintype "passive"))
      (node (ref "U302") (pin "3") (pinfunction "VOUT_3") (pintype "power_in"))
    )
    (net (code "45") (name "DP5VS") (class "Default")
      (node (ref "C305") (pin "2") (pinfunction "2_2") (pintype "passive"))
      (node (ref "C306") (pin "2") (pinfunction "2_2") (pintype "passive"))
      (node (ref "C307") (pin "2") (pinfunction "2_2") (pintype "passive"))
      (node (ref "C310") (pin "2") (pinfunction "2_2") (pintype "passive"))
      (node (ref "C316") (pin "2") (pinfunction "2_2") (pintype "passive"))
      (node (ref "C317") (pin "2") (pinfunction "2_2") (pintype "passive"))
      (node (ref "C318") (pin "2") (pinfunction "2_2") (pintype "passive"))
      (node (ref "C319") (pin "2") (pinfunction "2_2") (pintype "passive"))
      (node (ref "C320") (pin "2") (pinfunction "2_2") (pintype "passive"))
      (node (ref "C321") (pin "2") (pinfunction "2_2") (pintype "passive"))
      (node (ref "U300") (pin "2") (pinfunction "VIN_LDO1/2_2") (pintype "passive"))
      (node (ref "U300") (pin "21") (pinfunction "VIN_DCDC1_21") (pintype "passive"))
      (node (ref "U300") (pin "22") (pinfunction "VIN_DCDC2_22") (pintype "passive"))
      (node (ref "U300") (pin "32") (pinfunction "VIN_DCDC3_32") (pintype "passive"))
      (node (ref "U300") (pin "39") (pinfunction "VIN_LS1/LDO3_39") (pintype "passive"))
      (node (ref "U300") (pin "42") (pinfunction "VIN_LS2/LDO4_42") (pintype "passive"))
      (node (ref "U300") (pin "7") (pinfunction "VOUT_SYS_1_7") (pintype "passive"))
      (node (ref "U300") (pin "8") (pinfunction "VOUT_SYS_2_8") (pintype "passive"))
      (node (ref "U301") (pin "3") (pinfunction "VIN_3") (pintype "passive"))
      (node (ref "U302") (pin "2") (pinfunction "VIN_2") (pintype "power_in"))
    )
    (net (code "46") (name "GNDPWR") (class "Default")
      (node (ref "CN300") (pin "2") (pinfunction "GND_2") (pintype "power_in"))
      (node (ref "CN300") (pin "3") (pinfunction "GND_3") (pintype "power_in"))
      (node (ref "R309") (pin "1") (pinfunction "1_1") (pintype "passive"))
    )
    (net (code "47") (name "IN5VS") (class "Default")
      (node (ref "C300") (pin "2") (pinfunction "2_2") (pintype "passive"))
      (node (ref "C313") (pin "2") (pinfunction "2_2") (pintype "passive"))
      (node (ref "C314") (pin "2") (pinfunction "2_2") (pintype "passive"))
      (node (ref "C315") (pin "2") (pinfunction "2_2") (pintype "passive"))
      (node (ref "D300") (pin "1") (pinfunction "1_1") (pintype "passive"))
      (node (ref "LED300") (pin "4") (pinfunction "Common_Anode_4") (pintype "passive"))
      (node (ref "R300") (pin "2") (pinfunction "2_2") (pintype "passive"))
      (node (ref "R302") (pin "2") (pinfunction "2_2") (pintype "passive"))
      (node (ref "R305") (pin "1") (pinfunction "1_1") (pintype "passive"))
      (node (ref "U300") (pin "10") (pinfunction "EXT_VIN_DC_10") (pintype "passive"))
    )
    (net (code "48") (name "Net-(D300-Pad2)") (class "Default")
      (node (ref "D300") (pin "2") (pinfunction "2_2") (pintype "passive"))
      (node (ref "D301") (pin "2") (pinfunction "2_2") (pintype "passive"))
      (node (ref "R304") (pin "2") (pinfunction "2_2") (pintype "passive"))
    )
    (net (code "49") (name "Net-(LED300-GREEN)") (class "Default")
      (node (ref "LED300") (pin "2") (pinfunction "GREEN_2") (pintype "passive"))
      (node (ref "R306") (pin "2") (pinfunction "2_2") (pintype "passive"))
    )
    (net (code "50") (name "Net-(LED301-GREEN)") (class "Default")
      (node (ref "LED301") (pin "2") (pinfunction "GREEN_2") (pintype "passive"))
      (node (ref "R318") (pin "2") (pinfunction "2_2") (pintype "passive"))
    )
    (net (code "51") (name "Net-(LED302-GREEN)") (class "Default")
      (node (ref "LED302") (pin "2") (pinfunction "GREEN_2") (pintype "passive"))
      (node (ref "R331") (pin "2") (pinfunction "2_2") (pintype "passive"))
    )
    (net (code "52") (name "Net-(LED303-GREEN)") (class "Default")
      (node (ref "LED303") (pin "2") (pinfunction "GREEN_2") (pintype "passive"))
      (node (ref "R334") (pin "2") (pinfunction "2_2") (pintype "passive"))
    )
    (net (code "53") (name "Net-(U300-VBAT_1)") (class "Default")
      (node (ref "R307") (pin "1") (pinfunction "1_1") (pintype "passive"))
      (node (ref "R308") (pin "2") (pinfunction "2_2") (pintype "passive"))
      (node (ref "U300") (pin "4") (pinfunction "VBAT_1_4") (pintype "passive"))
      (node (ref "U300") (pin "5") (pinfunction "VBAT_2_5") (pintype "passive"))
    )
    (net (code "54") (name "Net-(U300-VBAT_SENSE)") (class "Default")
      (node (ref "R308") (pin "1") (pinfunction "1_1") (pintype "passive"))
      (node (ref "U300") (pin "6") (pinfunction "VBAT_SENSE_6") (pintype "passive"))
    )
    (net (code "55") (name "USB_5VS") (class "Default")
      (node (ref "C322") (pin "2") (pinfunction "2_2") (pintype "passive"))
      (node (ref "D301") (pin "1") (pinfunction "1_1") (pintype "passive"))
      (node (ref "R301") (pin "1") (pinfunction "1_1") (pintype "passive"))
      (node (ref "R303") (pin "2") (pinfunction "2_2") (pintype "passive"))
      (node (ref "U300") (pin "12") (pinfunction "EXT_VIN_USB_12") (pintype "passive"))
    )
    (net (code "56") (name "unconnected-(U300-FB_WLED-Pad38)") (class "Default")
      (node (ref "U300") (pin "38") (pinfunction "FB_WLED_38") (pintype "passive+no_connect"))
    )
    (net (code "57") (name "unconnected-(U300-ISET1-Pad35)") (class "Default")
      (node (ref "U300") (pin "35") (pinfunction "ISET1_35") (pintype "passive+no_connect"))
    )
    (net (code "58") (name "unconnected-(U300-ISET2-Pad36)") (class "Default")
      (node (ref "U300") (pin "36") (pinfunction "ISET2_36") (pintype "passive+no_connect"))
    )
    (net (code "59") (name "unconnected-(U300-ISINK1-Pad34)") (class "Default")
      (node (ref "U300") (pin "34") (pinfunction "ISINK1_34") (pintype "passive+no_connect"))
    )
    (net (code "60") (name "unconnected-(U300-ISINK2-Pad33)") (class "Default")
      (node (ref "U300") (pin "33") (pinfunction "ISINK2_33") (pintype "passive+no_connect"))
    )
    (net (code "61") (name "unconnected-(U300-L4-Pad37)") (class "Default")
      (node (ref "U300") (pin "37") (pinfunction "L4_37") (pintype "passive+no_connect"))
    )
    (net (code "62") (name "unconnected-(U300-MUX_IN-Pad14)") (class "Default")
      (node (ref "U300") (pin "14") (pinfunction "MUX_IN_14") (pintype "passive+no_connect"))
    )
    (net (code "63") (name "unconnected-(U300-MUX_OUT-Pad16)") (class "Default")
      (node (ref "U300") (pin "16") (pinfunction "MUX_OUT_16") (pintype "passive+no_connect"))
    )
    (net (code "64") (name "unconnected-(U300-NC1-Pad15)") (class "Default")
      (node (ref "U300") (pin "15") (pinfunction "NC1_15") (pintype "passive+no_connect"))
    )
    (net (code "65") (name "unconnected-(U300-NC2-Pad17)") (class "Default")
      (node (ref "U300") (pin "17") (pinfunction "NC2_17") (pintype "passive+no_connect"))
    )
    (net (code "66") (name "unconnected-(U300-TS-Pad11)") (class "Default")
      (node (ref "U300") (pin "11") (pinfunction "TS_11") (pintype "passive+no_connect"))
    )
  )
)
